# Wireless_Steering_v3_4.net
KiCad netlist of a schematic drawn in EAGLE
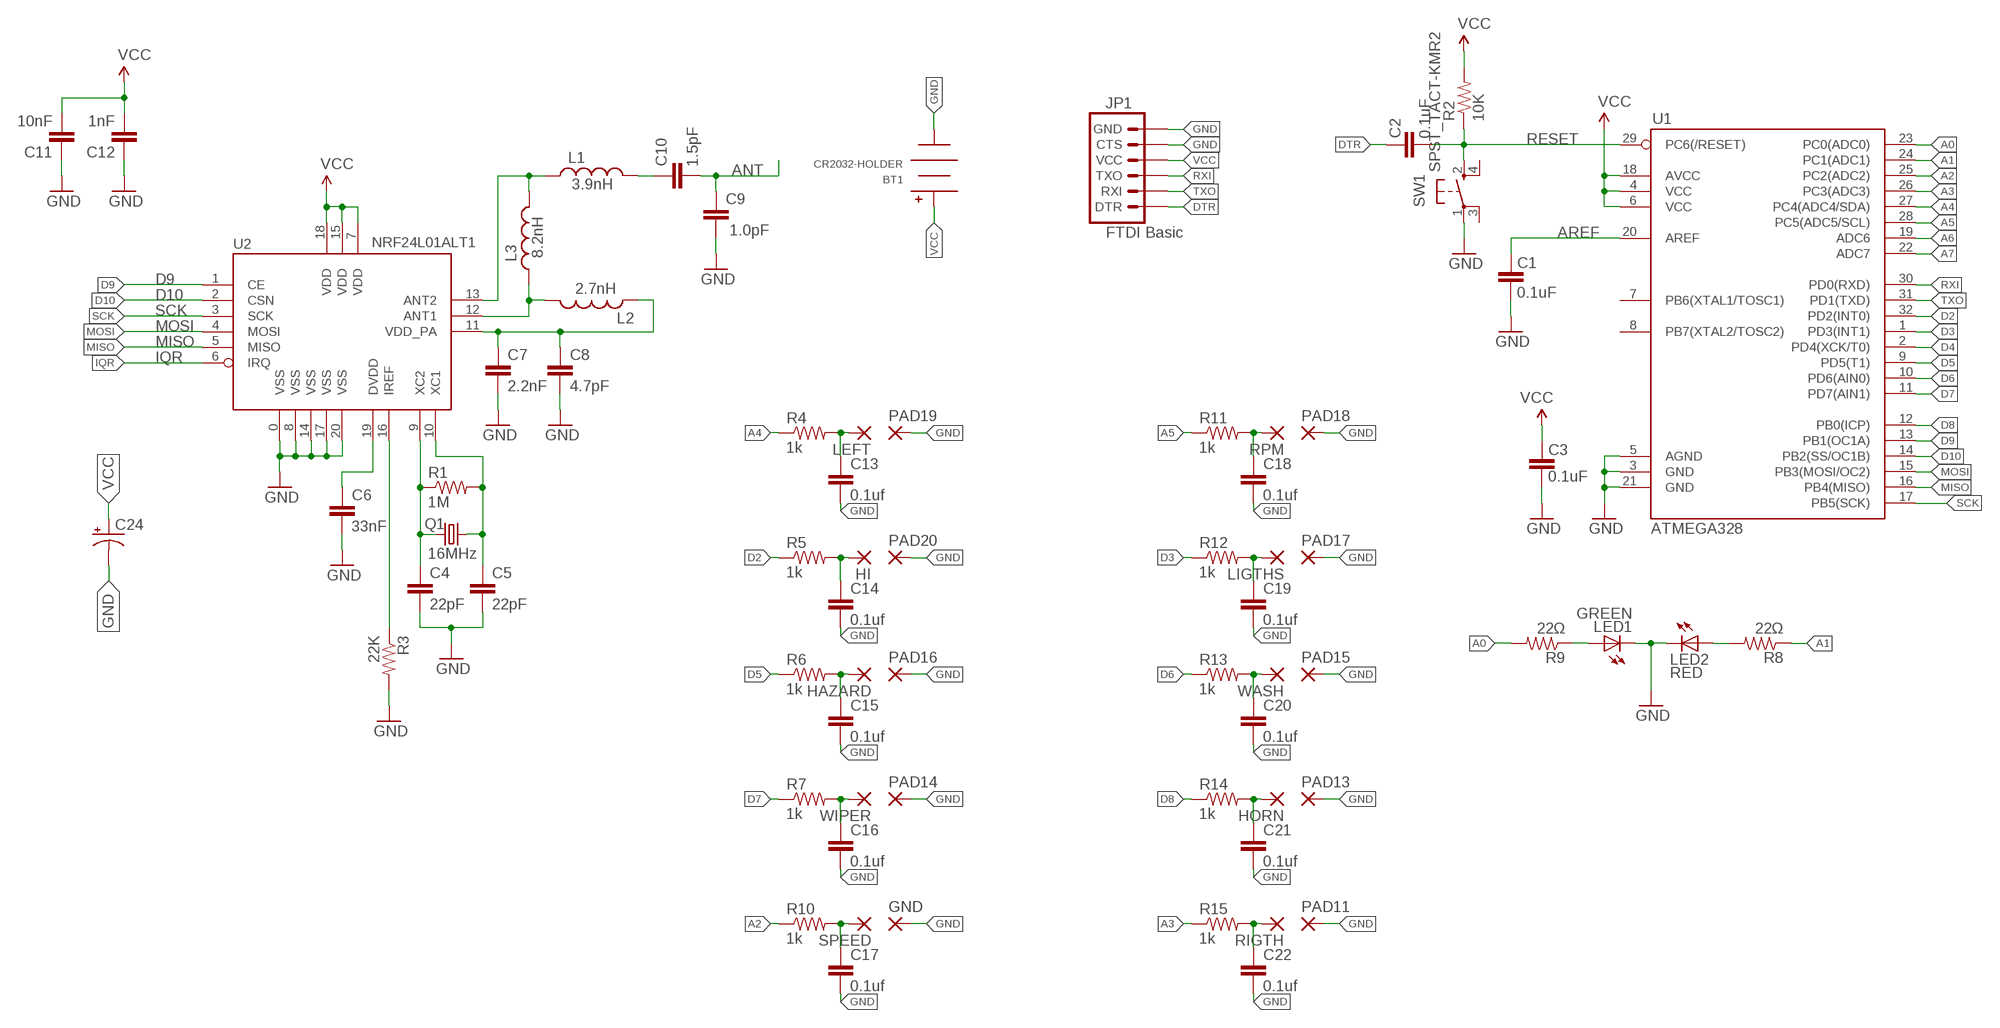
[diagram p0: schematic, sheet 1]

(export (version "E")
  (design (tool "Eeschema 10.0.6"))
  (components
    (comp (ref "BT1")
      (value "CR2032-HOLDER")
      (footprint "eagle-import:CH28-2032LF")
      (libsource (lib "eagle-import") (part "CR2032-HOLDER"))
    )
    (comp (ref "C1")
      (value "0.1uF")
      (footprint "eagle-import:0402-CAP")
      (libsource (lib "eagle-import") (part "CAP0402-CAP"))
    )
    (comp (ref "C2")
      (value "0.1uF")
      (footprint "eagle-import:0402-CAP")
      (libsource (lib "eagle-import") (part "CAP0402-CAP"))
    )
    (comp (ref "C3")
      (value "0.1uF")
      (footprint "eagle-import:0402-CAP")
      (libsource (lib "eagle-import") (part "CAP0402-CAP"))
    )
    (comp (ref "C4")
      (value "22pF")
      (footprint "eagle-import:0402-CAP")
      (libsource (lib "eagle-import") (part "CAP0402-CAP"))
    )
    (comp (ref "C5")
      (value "22pF")
      (footprint "eagle-import:0402-CAP")
      (libsource (lib "eagle-import") (part "CAP0402-CAP"))
    )
    (comp (ref "C6")
      (value "33nF")
      (footprint "eagle-import:0402-CAP")
      (libsource (lib "eagle-import") (part "CAP0402-CAP"))
    )
    (comp (ref "C7")
      (value "2.2nF")
      (footprint "eagle-import:0402-CAP")
      (libsource (lib "eagle-import") (part "CAP0402-CAP"))
    )
    (comp (ref "C8")
      (value "4.7pF")
      (footprint "eagle-import:0402-CAP")
      (libsource (lib "eagle-import") (part "CAP0402-CAP"))
    )
    (comp (ref "C9")
      (value "1.0pF")
      (footprint "eagle-import:0402-CAP")
      (libsource (lib "eagle-import") (part "CAP0402-CAP"))
    )
    (comp (ref "C10")
      (value "1.5pF")
      (footprint "eagle-import:0402-CAP")
      (libsource (lib "eagle-import") (part "CAP0402-CAP"))
    )
    (comp (ref "C11")
      (value "10nF")
      (footprint "eagle-import:0402-CAP")
      (libsource (lib "eagle-import") (part "CAP0402-CAP"))
    )
    (comp (ref "C12")
      (value "1nF")
      (footprint "eagle-import:0402-CAP")
      (libsource (lib "eagle-import") (part "CAP0402-CAP"))
    )
    (comp (ref "C13")
      (value "0.1uf")
      (footprint "eagle-import:0402-CAP")
      (libsource (lib "eagle-import") (part "CAP0402-CAP"))
    )
    (comp (ref "C14")
      (value "0.1uf")
      (footprint "eagle-import:0402-CAP")
      (libsource (lib "eagle-import") (part "CAP0402-CAP"))
    )
    (comp (ref "C15")
      (value "0.1uf")
      (footprint "eagle-import:0402-CAP")
      (libsource (lib "eagle-import") (part "CAP0402-CAP"))
    )
    (comp (ref "C16")
      (value "0.1uf")
      (footprint "eagle-import:0402-CAP")
      (libsource (lib "eagle-import") (part "CAP0402-CAP"))
    )
    (comp (ref "C17")
      (value "0.1uf")
      (footprint "eagle-import:0402-CAP")
      (libsource (lib "eagle-import") (part "CAP0402-CAP"))
    )
    (comp (ref "C18")
      (value "0.1uf")
      (footprint "eagle-import:0402-CAP")
      (libsource (lib "eagle-import") (part "CAP0402-CAP"))
    )
    (comp (ref "C19")
      (value "0.1uf")
      (footprint "eagle-import:0402-CAP")
      (libsource (lib "eagle-import") (part "CAP0402-CAP"))
    )
    (comp (ref "C20")
      (value "0.1uf")
      (footprint "eagle-import:0402-CAP")
      (libsource (lib "eagle-import") (part "CAP0402-CAP"))
    )
    (comp (ref "C21")
      (value "0.1uf")
      (footprint "eagle-import:0402-CAP")
      (libsource (lib "eagle-import") (part "CAP0402-CAP"))
    )
    (comp (ref "C22")
      (value "0.1uf")
      (footprint "eagle-import:0402-CAP")
      (libsource (lib "eagle-import") (part "CAP0402-CAP"))
    )
    (comp (ref "C24")
      (value "CAP_POL1206")
      (footprint "eagle-import:EIA3216")
      (libsource (lib "eagle-import") (part "CAP_POL1206"))
    )
    (comp (ref "GND")
      (value "SMD2")
      (footprint "eagle-import:SMD1,27-2,54")
      (libsource (lib "eagle-import") (part "SMD2"))
    )
    (comp (ref "HAZARD")
      (value "SMD2")
      (footprint "eagle-import:SMD1,27-2,54")
      (libsource (lib "eagle-import") (part "SMD2"))
    )
    (comp (ref "HI")
      (value "SMD2")
      (footprint "eagle-import:SMD1,27-2,54")
      (libsource (lib "eagle-import") (part "SMD2"))
    )
    (comp (ref "HORN")
      (value "SMD2")
      (footprint "eagle-import:SMD1,27-2,54")
      (libsource (lib "eagle-import") (part "SMD2"))
    )
    (comp (ref "JP1")
      (value "FTDI Basic")
      (footprint "eagle-import:1X06")
      (libsource (lib "eagle-import") (part "ARDUINO_SERIAL_PROGRAMPTH"))
    )
    (comp (ref "L1")
      (value "3.9nH")
      (footprint "eagle-import:C0402")
      (libsource (lib "eagle-import") (part "INDUCTOR0402"))
    )
    (comp (ref "L2")
      (value "2.7nH")
      (footprint "eagle-import:C0402")
      (libsource (lib "eagle-import") (part "INDUCTOR0402"))
    )
    (comp (ref "L3")
      (value "8.2nH")
      (footprint "eagle-import:C0402")
      (libsource (lib "eagle-import") (part "INDUCTOR0402"))
    )
    (comp (ref "LED1")
      (value "GREEN")
      (footprint "eagle-import:CHIP-LED0603")
      (libsource (lib "eagle-import") (part "LEDCHIP-LED0603"))
    )
    (comp (ref "LED2")
      (value "RED")
      (footprint "eagle-import:CHIP-LED0603")
      (libsource (lib "eagle-import") (part "LEDCHIP-LED0603"))
    )
    (comp (ref "LEFT")
      (value "SMD2")
      (footprint "eagle-import:SMD1,27-2,54")
      (libsource (lib "eagle-import") (part "SMD2"))
    )
    (comp (ref "LIGTHS")
      (value "SMD2")
      (footprint "eagle-import:SMD1,27-2,54")
      (libsource (lib "eagle-import") (part "SMD2"))
    )
    (comp (ref "PAD11")
      (value "SMD2")
      (footprint "eagle-import:SMD1,27-2,54")
      (libsource (lib "eagle-import") (part "SMD2"))
    )
    (comp (ref "PAD13")
      (value "SMD2")
      (footprint "eagle-import:SMD1,27-2,54")
      (libsource (lib "eagle-import") (part "SMD2"))
    )
    (comp (ref "PAD14")
      (value "SMD2")
      (footprint "eagle-import:SMD1,27-2,54")
      (libsource (lib "eagle-import") (part "SMD2"))
    )
    (comp (ref "PAD15")
      (value "SMD2")
      (footprint "eagle-import:SMD1,27-2,54")
      (libsource (lib "eagle-import") (part "SMD2"))
    )
    (comp (ref "PAD16")
      (value "SMD2")
      (footprint "eagle-import:SMD1,27-2,54")
      (libsource (lib "eagle-import") (part "SMD2"))
    )
    (comp (ref "PAD17")
      (value "SMD2")
      (footprint "eagle-import:SMD1,27-2,54")
      (libsource (lib "eagle-import") (part "SMD2"))
    )
    (comp (ref "PAD18")
      (value "SMD2")
      (footprint "eagle-import:SMD1,27-2,54")
      (libsource (lib "eagle-import") (part "SMD2"))
    )
    (comp (ref "PAD19")
      (value "SMD2")
      (footprint "eagle-import:SMD1,27-2,54")
      (libsource (lib "eagle-import") (part "SMD2"))
    )
    (comp (ref "PAD20")
      (value "SMD2")
      (footprint "eagle-import:SMD1,27-2,54")
      (libsource (lib "eagle-import") (part "SMD2"))
    )
    (comp (ref "Q1")
      (value "16MHz")
      (footprint "eagle-import:CRYSTAL-SMD-5X3")
      (libsource (lib "eagle-import") (part "CRYSTAL5X3"))
    )
    (comp (ref "R1")
      (value "1M")
      (footprint "eagle-import:0402-RES")
      (libsource (lib "eagle-import") (part "RESISTOR0402-RES"))
    )
    (comp (ref "R2")
      (value "10K")
      (footprint "eagle-import:0402-RES")
      (libsource (lib "eagle-import") (part "RESISTOR0402-RES"))
    )
    (comp (ref "R3")
      (value "22K")
      (footprint "eagle-import:0402-RES")
      (libsource (lib "eagle-import") (part "RESISTOR0402-RES"))
    )
    (comp (ref "R4")
      (value "1k")
      (footprint "eagle-import:R0402")
      (libsource (lib "eagle-import") (part "R-US_R0402"))
    )
    (comp (ref "R5")
      (value "1k")
      (footprint "eagle-import:R0402")
      (libsource (lib "eagle-import") (part "R-US_R0402"))
    )
    (comp (ref "R6")
      (value "1k")
      (footprint "eagle-import:R0402")
      (libsource (lib "eagle-import") (part "R-US_R0402"))
    )
    (comp (ref "R7")
      (value "1k")
      (footprint "eagle-import:R0402")
      (libsource (lib "eagle-import") (part "R-US_R0402"))
    )
    (comp (ref "R8")
      (value "22Ω")
      (footprint "eagle-import:R0402")
      (libsource (lib "eagle-import") (part "R-US_R0402"))
    )
    (comp (ref "R9")
      (value "22Ω")
      (footprint "eagle-import:R0402")
      (libsource (lib "eagle-import") (part "R-US_R0402"))
    )
    (comp (ref "R10")
      (value "1k")
      (footprint "eagle-import:R0402")
      (libsource (lib "eagle-import") (part "R-US_R0402"))
    )
    (comp (ref "R11")
      (value "1k")
      (footprint "eagle-import:R0402")
      (libsource (lib "eagle-import") (part "R-US_R0402"))
    )
    (comp (ref "R12")
      (value "1k")
      (footprint "eagle-import:R0402")
      (libsource (lib "eagle-import") (part "R-US_R0402"))
    )
    (comp (ref "R13")
      (value "1k")
      (footprint "eagle-import:R0402")
      (libsource (lib "eagle-import") (part "R-US_R0402"))
    )
    (comp (ref "R14")
      (value "1k")
      (footprint "eagle-import:R0402")
      (libsource (lib "eagle-import") (part "R-US_R0402"))
    )
    (comp (ref "R15")
      (value "1k")
      (footprint "eagle-import:R0402")
      (libsource (lib "eagle-import") (part "R-US_R0402"))
    )
    (comp (ref "RIGTH")
      (value "SMD2")
      (footprint "eagle-import:SMD1,27-2,54")
      (libsource (lib "eagle-import") (part "SMD2"))
    )
    (comp (ref "RPM")
      (value "SMD2")
      (footprint "eagle-import:SMD1,27-2,54")
      (libsource (lib "eagle-import") (part "SMD2"))
    )
    (comp (ref "SPEED")
      (value "SMD2")
      (footprint "eagle-import:SMD1,27-2,54")
      (libsource (lib "eagle-import") (part "SMD2"))
    )
    (comp (ref "SW1")
      (value "SPST_TACT-KMR2")
      (footprint "eagle-import:KMR2")
      (libsource (lib "eagle-import") (part "SPST_TACT-KMR2"))
    )
    (comp (ref "U1")
      (value "ATMEGA328")
      (footprint "eagle-import:TQFP32-08")
      (libsource (lib "eagle-import") (part "ATMEGA168"))
    )
    (comp (ref "U2")
      (value "NRF24L01ALT1")
      (footprint "eagle-import:QFN20_ALT1")
      (libsource (lib "eagle-import") (part "NRF24L01ALT1"))
    )
    (comp (ref "WASH")
      (value "SMD2")
      (footprint "eagle-import:SMD1,27-2,54")
      (libsource (lib "eagle-import") (part "SMD2"))
    )
    (comp (ref "WIPER")
      (value "SMD2")
      (footprint "eagle-import:SMD1,27-2,54")
      (libsource (lib "eagle-import") (part "SMD2"))
    )
  )
  (nets
    (net (code "1") (name "/ANT") (class "Default")
      (node (ref "C10") (pin "2") (pinfunction "2_2") (pintype "passive"))
      (node (ref "C9") (pin "2") (pinfunction "2_2") (pintype "passive"))
    )
    (net (code "2") (name "/AREF") (class "Default")
      (node (ref "C1") (pin "2") (pinfunction "2_2") (pintype "passive"))
      (node (ref "U1") (pin "20") (pinfunction "AREF_20") (pintype "bidirectional"))
    )
    (net (code "3") (name "/RESET") (class "Default")
      (node (ref "C2") (pin "1") (pinfunction "1_1") (pintype "passive"))
      (node (ref "R2") (pin "1") (pinfunction "1_1") (pintype "passive"))
      (node (ref "SW1") (pin "2") (pinfunction "S_2") (pintype "passive"))
      (node (ref "U1") (pin "29") (pinfunction "PC6(/RESET)_29") (pintype "bidirectional"))
    )
    (net (code "4") (name "A0") (class "Default")
      (node (ref "R9") (pin "2") (pinfunction "2_2") (pintype "passive"))
      (node (ref "U1") (pin "23") (pinfunction "PC0(ADC0)_23") (pintype "bidirectional"))
    )
    (net (code "5") (name "A1") (class "Default")
      (node (ref "R8") (pin "1") (pinfunction "1_1") (pintype "passive"))
      (node (ref "U1") (pin "24") (pinfunction "PC1(ADC1)_24") (pintype "bidirectional"))
    )
    (net (code "6") (name "A2") (class "Default")
      (node (ref "R10") (pin "1") (pinfunction "1_1") (pintype "passive"))
      (node (ref "U1") (pin "25") (pinfunction "PC2(ADC2)_25") (pintype "bidirectional"))
    )
    (net (code "7") (name "A3") (class "Default")
      (node (ref "R15") (pin "1") (pinfunction "1_1") (pintype "passive"))
      (node (ref "U1") (pin "26") (pinfunction "PC3(ADC3)_26") (pintype "bidirectional"))
    )
    (net (code "8") (name "A4") (class "Default")
      (node (ref "R4") (pin "1") (pinfunction "1_1") (pintype "passive"))
      (node (ref "U1") (pin "27") (pinfunction "PC4(ADC4/SDA)_27") (pintype "bidirectional"))
    )
    (net (code "9") (name "A5") (class "Default")
      (node (ref "R11") (pin "1") (pinfunction "1_1") (pintype "passive"))
      (node (ref "U1") (pin "28") (pinfunction "PC5(ADC5/SCL)_28") (pintype "bidirectional"))
    )
    (net (code "10") (name "A6") (class "Default")
      (node (ref "U1") (pin "19") (pinfunction "ADC6_19") (pintype "bidirectional"))
    )
    (net (code "11") (name "A7") (class "Default")
      (node (ref "U1") (pin "22") (pinfunction "ADC7_22") (pintype "bidirectional"))
    )
    (net (code "12") (name "D2") (class "Default")
      (node (ref "R5") (pin "1") (pinfunction "1_1") (pintype "passive"))
      (node (ref "U1") (pin "32") (pinfunction "PD2(INT0)_32") (pintype "bidirectional"))
    )
    (net (code "13") (name "D3") (class "Default")
      (node (ref "R12") (pin "1") (pinfunction "1_1") (pintype "passive"))
      (node (ref "U1") (pin "1") (pinfunction "PD3(INT1)_1") (pintype "bidirectional"))
    )
    (net (code "14") (name "D4") (class "Default")
      (node (ref "U1") (pin "2") (pinfunction "PD4(XCK/T0)_2") (pintype "bidirectional"))
    )
    (net (code "15") (name "D5") (class "Default")
      (node (ref "R6") (pin "1") (pinfunction "1_1") (pintype "passive"))
      (node (ref "U1") (pin "9") (pinfunction "PD5(T1)_9") (pintype "bidirectional"))
    )
    (net (code "16") (name "D6") (class "Default")
      (node (ref "R13") (pin "1") (pinfunction "1_1") (pintype "passive"))
      (node (ref "U1") (pin "10") (pinfunction "PD6(AIN0)_10") (pintype "bidirectional"))
    )
    (net (code "17") (name "D7") (class "Default")
      (node (ref "R7") (pin "1") (pinfunction "1_1") (pintype "passive"))
      (node (ref "U1") (pin "11") (pinfunction "PD7(AIN1)_11") (pintype "bidirectional"))
    )
    (net (code "18") (name "D8") (class "Default")
      (node (ref "R14") (pin "1") (pinfunction "1_1") (pintype "passive"))
      (node (ref "U1") (pin "12") (pinfunction "PB0(ICP)_12") (pintype "bidirectional"))
    )
    (net (code "19") (name "D9") (class "Default")
      (node (ref "U1") (pin "13") (pinfunction "PB1(OC1A)_13") (pintype "bidirectional"))
      (node (ref "U2") (pin "1") (pinfunction "CE_1") (pintype "input"))
    )
    (net (code "20") (name "D10") (class "Default")
      (node (ref "U1") (pin "14") (pinfunction "PB2(SS/OC1B)_14") (pintype "bidirectional"))
      (node (ref "U2") (pin "2") (pinfunction "CSN_2") (pintype "input"))
    )
    (net (code "21") (name "DTR") (class "Default")
      (node (ref "C2") (pin "2") (pinfunction "2_2") (pintype "passive"))
      (node (ref "JP1") (pin "1") (pinfunction "DTR_1") (pintype "passive"))
    )
    (net (code "22") (name "GND") (class "Default")
      (node (ref "BT1") (pin "NEG") (pinfunction "NEG_NEG") (pintype "bidirectional"))
      (node (ref "C1") (pin "1") (pinfunction "1_1") (pintype "passive"))
      (node (ref "C11") (pin "1") (pinfunction "1_1") (pintype "passive"))
      (node (ref "C12") (pin "1") (pinfunction "1_1") (pintype "passive"))
      (node (ref "C13") (pin "2") (pinfunction "2_2") (pintype "passive"))
      (node (ref "C14") (pin "2") (pinfunction "2_2") (pintype "passive"))
      (node (ref "C15") (pin "2") (pinfunction "2_2") (pintype "passive"))
      (node (ref "C16") (pin "2") (pinfunction "2_2") (pintype "passive"))
      (node (ref "C17") (pin "2") (pinfunction "2_2") (pintype "passive"))
      (node (ref "C18") (pin "2") (pinfunction "2_2") (pintype "passive"))
      (node (ref "C19") (pin "2") (pinfunction "2_2") (pintype "passive"))
      (node (ref "C20") (pin "2") (pinfunction "2_2") (pintype "passive"))
      (node (ref "C21") (pin "2") (pinfunction "2_2") (pintype "passive"))
      (node (ref "C22") (pin "2") (pinfunction "2_2") (pintype "passive"))
      (node (ref "C24") (pin "C") (pinfunction "-_C") (pintype "passive"))
      (node (ref "C3") (pin "1") (pinfunction "1_1") (pintype "passive"))
      (node (ref "C4") (pin "2") (pinfunction "2_2") (pintype "passive"))
      (node (ref "C5") (pin "2") (pinfunction "2_2") (pintype "passive"))
      (node (ref "C6") (pin "2") (pinfunction "2_2") (pintype "passive"))
      (node (ref "C7") (pin "2") (pinfunction "2_2") (pintype "passive"))
      (node (ref "C8") (pin "2") (pinfunction "2_2") (pintype "passive"))
      (node (ref "C9") (pin "1") (pinfunction "1_1") (pintype "passive"))
      (node (ref "GND") (pin "1") (pinfunction "P_1") (pintype "passive"))
      (node (ref "JP1") (pin "5") (pinfunction "CTS_5") (pintype "passive"))
      (node (ref "JP1") (pin "6") (pinfunction "GND_6") (pintype "passive"))
      (node (ref "LED1") (pin "C") (pinfunction "C_C") (pintype "passive"))
      (node (ref "LED2") (pin "C") (pinfunction "C_C") (pintype "passive"))
      (node (ref "PAD11") (pin "1") (pinfunction "P_1") (pintype "passive"))
      (node (ref "PAD13") (pin "1") (pinfunction "P_1") (pintype "passive"))
      (node (ref "PAD14") (pin "1") (pinfunction "P_1") (pintype "passive"))
      (node (ref "PAD15") (pin "1") (pinfunction "P_1") (pintype "passive"))
      (node (ref "PAD16") (pin "1") (pinfunction "P_1") (pintype "passive"))
      (node (ref "PAD17") (pin "1") (pinfunction "P_1") (pintype "passive"))
      (node (ref "PAD18") (pin "1") (pinfunction "P_1") (pintype "passive"))
      (node (ref "PAD19") (pin "1") (pinfunction "P_1") (pintype "passive"))
      (node (ref "PAD20") (pin "1") (pinfunction "P_1") (pintype "passive"))
      (node (ref "R3") (pin "2") (pinfunction "2_2") (pintype "passive"))
      (node (ref "SW1") (pin "1") (pinfunction "P_1") (pintype "passive"))
      (node (ref "U1") (pin "21") (pinfunction "GND_21") (pintype "bidirectional"))
      (node (ref "U1") (pin "3") (pinfunction "GND_3") (pintype "bidirectional"))
      (node (ref "U1") (pin "5") (pinfunction "AGND_5") (pintype "bidirectional"))
      (node (ref "U2") (pin "0") (pinfunction "VSS_0") (pintype "power_in"))
      (node (ref "U2") (pin "14") (pinfunction "VSS_14") (pintype "power_in"))
      (node (ref "U2") (pin "17") (pinfunction "VSS_17") (pintype "power_in"))
      (node (ref "U2") (pin "20") (pinfunction "VSS_20") (pintype "power_in"))
      (node (ref "U2") (pin "8") (pinfunction "VSS_8") (pintype "power_in"))
    )
    (net (code "23") (name "IQR") (class "Default")
      (node (ref "U2") (pin "6") (pinfunction "IRQ_6") (pintype "output"))
    )
    (net (code "24") (name "MISO") (class "Default")
      (node (ref "U1") (pin "16") (pinfunction "PB4(MISO)_16") (pintype "bidirectional"))
      (node (ref "U2") (pin "5") (pinfunction "MISO_5") (pintype "output"))
    )
    (net (code "25") (name "MOSI") (class "Default")
      (node (ref "U1") (pin "15") (pinfunction "PB3(MOSI/OC2)_15") (pintype "bidirectional"))
      (node (ref "U2") (pin "4") (pinfunction "MOSI_4") (pintype "input"))
    )
    (net (code "26") (name "Net-(C10-Pad1)") (class "Default")
      (node (ref "C10") (pin "1") (pinfunction "1_1") (pintype "passive"))
      (node (ref "L1") (pin "2") (pinfunction "2_2") (pintype "passive"))
    )
    (net (code "27") (name "Net-(HAZARD-P)") (class "Default")
      (node (ref "C15") (pin "1") (pinfunction "1_1") (pintype "passive"))
      (node (ref "HAZARD") (pin "1") (pinfunction "P_1") (pintype "passive"))
      (node (ref "R6") (pin "2") (pinfunction "2_2") (pintype "passive"))
    )
    (net (code "28") (name "Net-(HI-P)") (class "Default")
      (node (ref "C14") (pin "1") (pinfunction "1_1") (pintype "passive"))
      (node (ref "HI") (pin "1") (pinfunction "P_1") (pintype "passive"))
      (node (ref "R5") (pin "2") (pinfunction "2_2") (pintype "passive"))
    )
    (net (code "29") (name "Net-(HORN-P)") (class "Default")
      (node (ref "C21") (pin "1") (pinfunction "1_1") (pintype "passive"))
      (node (ref "HORN") (pin "1") (pinfunction "P_1") (pintype "passive"))
      (node (ref "R14") (pin "2") (pinfunction "2_2") (pintype "passive"))
    )
    (net (code "30") (name "Net-(LED1-PadA)") (class "Default")
      (node (ref "LED1") (pin "A") (pinfunction "A_A") (pintype "passive"))
      (node (ref "R9") (pin "1") (pinfunction "1_1") (pintype "passive"))
    )
    (net (code "31") (name "Net-(LED2-PadA)") (class "Default")
      (node (ref "LED2") (pin "A") (pinfunction "A_A") (pintype "passive"))
      (node (ref "R8") (pin "2") (pinfunction "2_2") (pintype "passive"))
    )
    (net (code "32") (name "Net-(LEFT-P)") (class "Default")
      (node (ref "C13") (pin "1") (pinfunction "1_1") (pintype "passive"))
      (node (ref "LEFT") (pin "1") (pinfunction "P_1") (pintype "passive"))
      (node (ref "R4") (pin "2") (pinfunction "2_2") (pintype "passive"))
    )
    (net (code "33") (name "Net-(LIGTHS-P)") (class "Default")
      (node (ref "C19") (pin "1") (pinfunction "1_1") (pintype "passive"))
      (node (ref "LIGTHS") (pin "1") (pinfunction "P_1") (pintype "passive"))
      (node (ref "R12") (pin "2") (pinfunction "2_2") (pintype "passive"))
    )
    (net (code "34") (name "Net-(Q1-2)") (class "Default")
      (node (ref "C5") (pin "1") (pinfunction "1_1") (pintype "passive"))
      (node (ref "Q1") (pin "3") (pinfunction "2_3") (pintype "passive"))
      (node (ref "R1") (pin "2") (pinfunction "2_2") (pintype "passive"))
      (node (ref "U2") (pin "10") (pinfunction "XC1_10") (pintype "input"))
    )
    (net (code "35") (name "Net-(RIGTH-P)") (class "Default")
      (node (ref "C22") (pin "1") (pinfunction "1_1") (pintype "passive"))
      (node (ref "R15") (pin "2") (pinfunction "2_2") (pintype "passive"))
      (node (ref "RIGTH") (pin "1") (pinfunction "P_1") (pintype "passive"))
    )
    (net (code "36") (name "Net-(RPM-P)") (class "Default")
      (node (ref "C18") (pin "1") (pinfunction "1_1") (pintype "passive"))
      (node (ref "R11") (pin "2") (pinfunction "2_2") (pintype "passive"))
      (node (ref "RPM") (pin "1") (pinfunction "P_1") (pintype "passive"))
    )
    (net (code "37") (name "Net-(SPEED-P)") (class "Default")
      (node (ref "C17") (pin "1") (pinfunction "1_1") (pintype "passive"))
      (node (ref "R10") (pin "2") (pinfunction "2_2") (pintype "passive"))
      (node (ref "SPEED") (pin "1") (pinfunction "P_1") (pintype "passive"))
    )
    (net (code "38") (name "Net-(U2-ANT1)") (class "Default")
      (node (ref "L2") (pin "2") (pinfunction "2_2") (pintype "passive"))
      (node (ref "L3") (pin "1") (pinfunction "1_1") (pintype "passive"))
      (node (ref "U2") (pin "12") (pinfunction "ANT1_12") (pintype "output"))
    )
    (net (code "39") (name "Net-(U2-ANT2)") (class "Default")
      (node (ref "L1") (pin "1") (pinfunction "1_1") (pintype "passive"))
      (node (ref "L3") (pin "2") (pinfunction "2_2") (pintype "passive"))
      (node (ref "U2") (pin "13") (pinfunction "ANT2_13") (pintype "output"))
    )
    (net (code "40") (name "Net-(U2-DVDD)") (class "Default")
      (node (ref "C6") (pin "1") (pinfunction "1_1") (pintype "passive"))
      (node (ref "U2") (pin "19") (pinfunction "DVDD_19") (pintype "power_in"))
    )
    (net (code "41") (name "Net-(U2-IREF)") (class "Default")
      (node (ref "R3") (pin "1") (pinfunction "1_1") (pintype "passive"))
      (node (ref "U2") (pin "16") (pinfunction "IREF_16") (pintype "input"))
    )
    (net (code "42") (name "Net-(U2-VDD_PA)") (class "Default")
      (node (ref "C7") (pin "1") (pinfunction "1_1") (pintype "passive"))
      (node (ref "C8") (pin "1") (pinfunction "1_1") (pintype "passive"))
      (node (ref "L2") (pin "1") (pinfunction "1_1") (pintype "passive"))
      (node (ref "U2") (pin "11") (pinfunction "VDD_PA_11") (pintype "power_in"))
    )
    (net (code "43") (name "Net-(U2-XC2)") (class "Default")
      (node (ref "C4") (pin "1") (pinfunction "1_1") (pintype "passive"))
      (node (ref "Q1") (pin "1") (pinfunction "1_1") (pintype "passive"))
      (node (ref "R1") (pin "1") (pinfunction "1_1") (pintype "passive"))
      (node (ref "U2") (pin "9") (pinfunction "XC2_9") (pintype "input"))
    )
    (net (code "44") (name "Net-(WASH-P)") (class "Default")
      (node (ref "C20") (pin "1") (pinfunction "1_1") (pintype "passive"))
      (node (ref "R13") (pin "2") (pinfunction "2_2") (pintype "passive"))
      (node (ref "WASH") (pin "1") (pinfunction "P_1") (pintype "passive"))
    )
    (net (code "45") (name "Net-(WIPER-P)") (class "Default")
      (node (ref "C16") (pin "1") (pinfunction "1_1") (pintype "passive"))
      (node (ref "R7") (pin "2") (pinfunction "2_2") (pintype "passive"))
      (node (ref "WIPER") (pin "1") (pinfunction "P_1") (pintype "passive"))
    )
    (net (code "46") (name "RXI") (class "Default")
      (node (ref "JP1") (pin "3") (pinfunction "TXO_3") (pintype "passive"))
      (node (ref "U1") (pin "30") (pinfunction "PD0(RXD)_30") (pintype "bidirectional"))
    )
    (net (code "47") (name "SCK") (class "Default")
      (node (ref "U1") (pin "17") (pinfunction "PB5(SCK)_17") (pintype "bidirectional"))
      (node (ref "U2") (pin "3") (pinfunction "SCK_3") (pintype "input"))
    )
    (net (code "48") (name "TXO") (class "Default")
      (node (ref "JP1") (pin "2") (pinfunction "RXI_2") (pintype "passive"))
      (node (ref "U1") (pin "31") (pinfunction "PD1(TXD)_31") (pintype "bidirectional"))
    )
    (net (code "49") (name "VCC") (class "Default")
      (node (ref "BT1") (pin "POS") (pinfunction "POS_POS") (pintype "bidirectional"))
      (node (ref "C11") (pin "2") (pinfunction "2_2") (pintype "passive"))
      (node (ref "C12") (pin "2") (pinfunction "2_2") (pintype "passive"))
      (node (ref "C24") (pin "A") (pinfunction "+_A") (pintype "passive"))
      (node (ref "C3") (pin "2") (pinfunction "2_2") (pintype "passive"))
      (node (ref "JP1") (pin "4") (pinfunction "VCC_4") (pintype "passive"))
      (node (ref "R2") (pin "2") (pinfunction "2_2") (pintype "passive"))
      (node (ref "U1") (pin "18") (pinfunction "AVCC_18") (pintype "bidirectional"))
      (node (ref "U1") (pin "4") (pinfunction "VCC_4") (pintype "bidirectional"))
      (node (ref "U1") (pin "6") (pinfunction "VCC_6") (pintype "bidirectional"))
      (node (ref "U2") (pin "15") (pinfunction "VDD_15") (pintype "power_in"))
      (node (ref "U2") (pin "18") (pinfunction "VDD_18") (pintype "power_in"))
      (node (ref "U2") (pin "7") (pinfunction "VDD_7") (pintype "power_in"))
    )
    (net (code "50") (name "unconnected-(SW1-P1-Pad3)") (class "Default")
      (node (ref "SW1") (pin "3") (pinfunction "P1_3") (pintype "passive"))
    )
    (net (code "51") (name "unconnected-(SW1-S1-Pad4)") (class "Default")
      (node (ref "SW1") (pin "4") (pinfunction "S1_4") (pintype "passive"))
    )
    (net (code "52") (name "unconnected-(U1-PB6(XTAL1{slash}TOSC1)-Pad7)") (class "Default")
      (node (ref "U1") (pin "7") (pinfunction "PB6(XTAL1/TOSC1)_7") (pintype "bidirectional"))
    )
    (net (code "53") (name "unconnected-(U1-PB7(XTAL2{slash}TOSC2)-Pad8)") (class "Default")
      (node (ref "U1") (pin "8") (pinfunction "PB7(XTAL2/TOSC2)_8") (pintype "bidirectional"))
    )
  )
)
